# LB_BIT_i23-threshold-v03_1_1.net
KiCad netlist of a schematic drawn in EAGLE
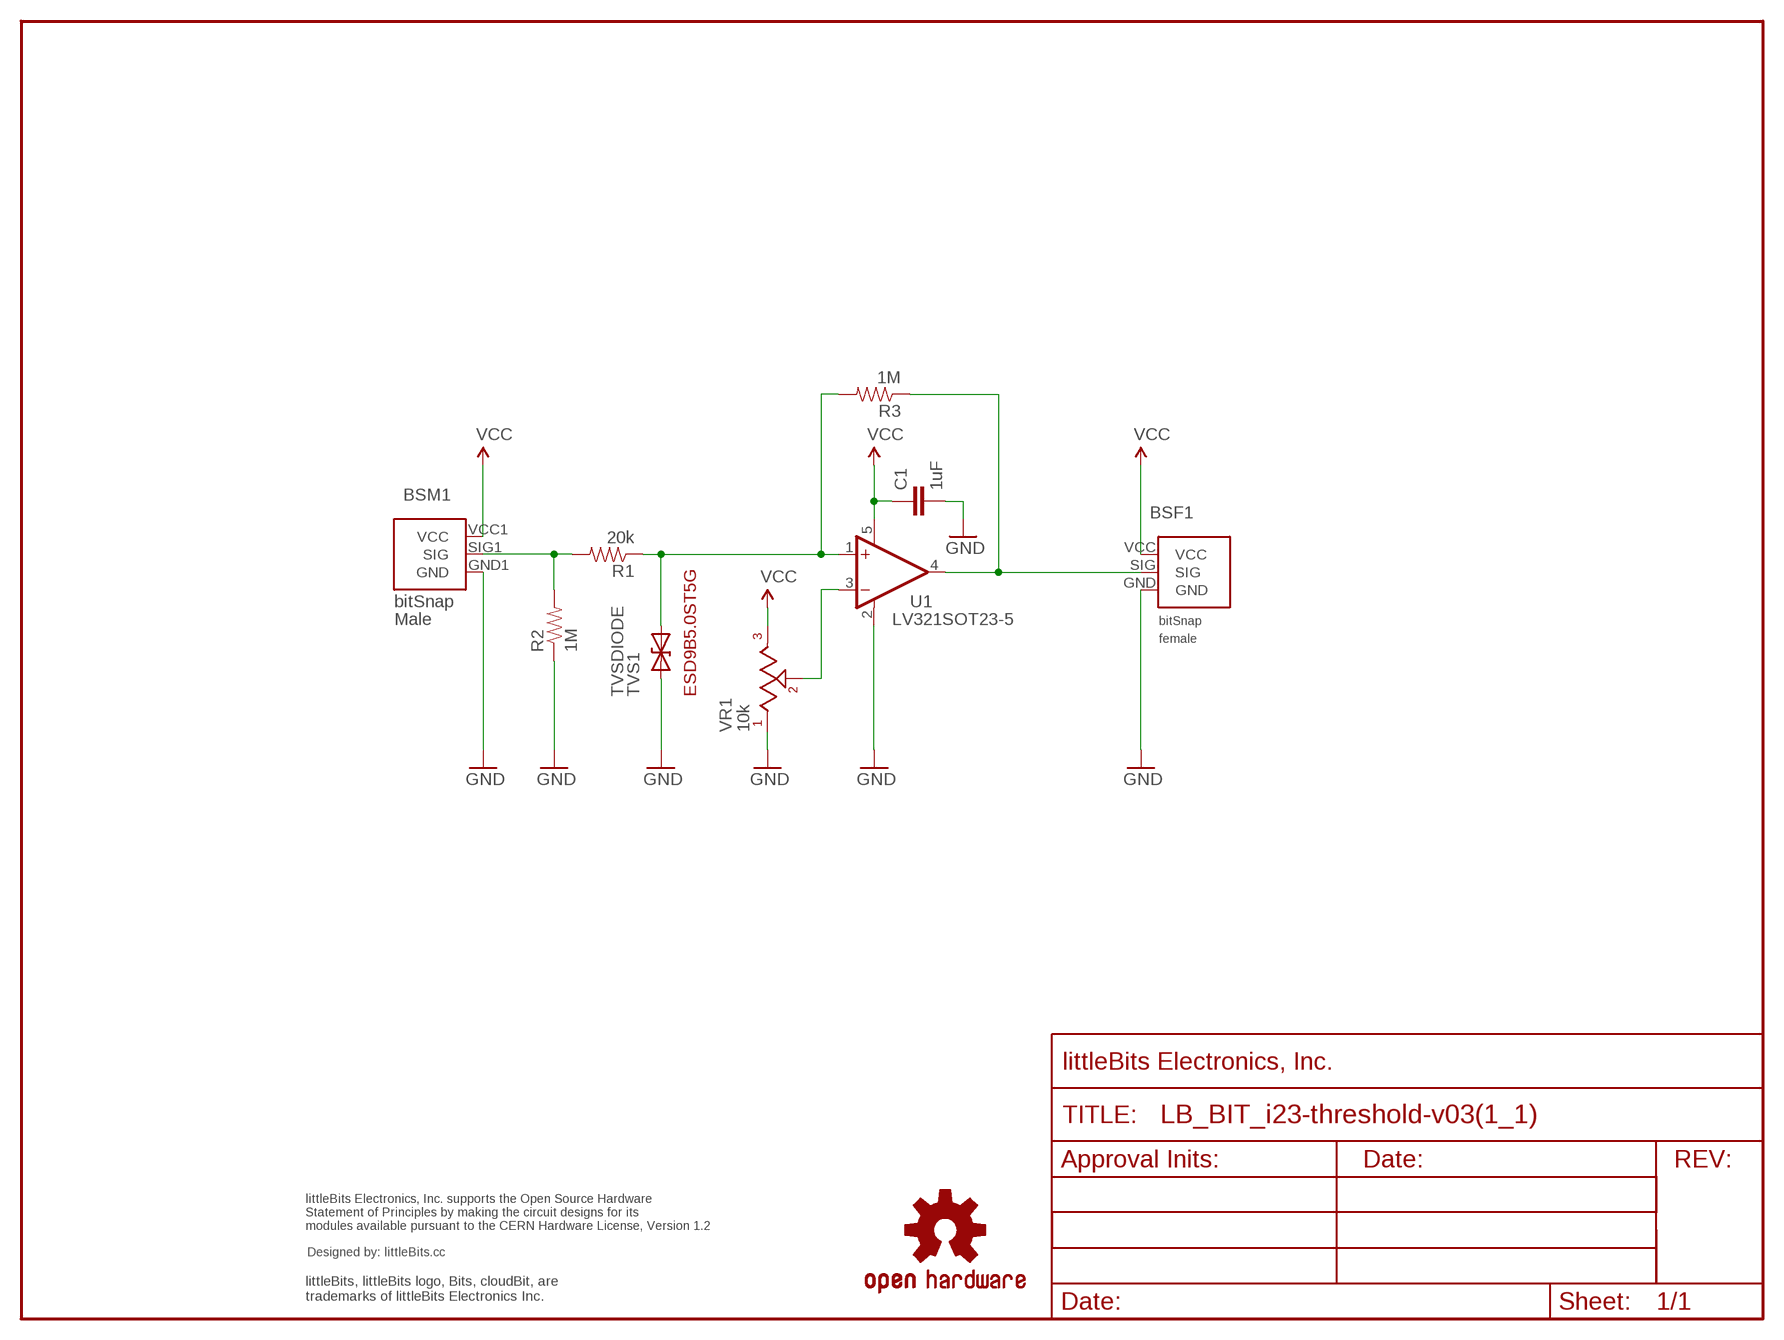
[diagram p0: schematic, sheet 1]

(export (version "E")
  (design (tool "Eeschema 10.0.6"))
  (components
    (comp (ref "BSF1")
      (value "BITSNAP_V03_FEMALE")
      (footprint "eagle-import:BITSNAP_V03_FEMALE")
      (libsource (lib "eagle-import") (part "BITSNAP_V03_FEMALE"))
    )
    (comp (ref "BSM1")
      (value "BITSNAP_V03_MALE")
      (footprint "eagle-import:BITSNAP_V03_MALE")
      (libsource (lib "eagle-import") (part "BITSNAP_V03_MALE"))
    )
    (comp (ref "C1")
      (value "1uF")
      (footprint "eagle-import:CAP-0603")
      (libsource (lib "eagle-import") (part "CAPCAP-0603"))
    )
    (comp (ref "R1")
      (value "20k")
      (footprint "eagle-import:RES-0603")
      (libsource (lib "eagle-import") (part "RESISTOR0603"))
    )
    (comp (ref "R2")
      (value "1M")
      (footprint "eagle-import:RES-0603")
      (libsource (lib "eagle-import") (part "RESISTOR0603"))
    )
    (comp (ref "R3")
      (value "1M")
      (footprint "eagle-import:RES-0603")
      (libsource (lib "eagle-import") (part "RESISTOR0603"))
    )
    (comp (ref "TVS1")
      (value "TVSDIODE")
      (footprint "eagle-import:SOD-923")
      (fields (field (name "MPN") "ESD9B5.0ST5G"))
      (libsource (lib "eagle-import") (part "DIODE-TVSSOD-923"))
    )
    (comp (ref "U$3")
      (value "OSHW-LOGOL")
      (footprint "eagle-import:OSHW-LOGO-L")
      (libsource (lib "eagle-import") (part "OSHW-LOGOL"))
    )
    (comp (ref "U$5")
      (value "FRAME-LETTER-OHWOHW")
      (footprint "eagle-import:FABDWG01-OHW")
      (libsource (lib "eagle-import") (part "FRAME-LETTER-OHWOHW"))
    )
    (comp (ref "U$31")
      (value "OSHWCREDIT")
      (footprint "eagle-import:OSHWCREDIT")
      (libsource (lib "eagle-import") (part "OSHWCREDIT"))
    )
    (comp (ref "U1")
      (value "LV321SOT23-5")
      (footprint "eagle-import:SOT23-5")
      (libsource (lib "eagle-import") (part "LV321SOT23-5"))
    )
    (comp (ref "VR1")
      (value "10k")
      (footprint "eagle-import:9MM_POT")
      (libsource (lib "eagle-import") (part "9MM_POT"))
    )
  )
  (nets
    (net (code "1") (name "GND") (class "Default")
      (node (ref "BSF1") (pin "GND") (pinfunction "GND_GND") (pintype "bidirectional"))
      (node (ref "BSM1") (pin "GND1") (pinfunction "GND_GND1") (pintype "bidirectional"))
      (node (ref "C1") (pin "2") (pinfunction "2_2") (pintype "passive"))
      (node (ref "R2") (pin "1") (pinfunction "1_1") (pintype "passive"))
      (node (ref "TVS1") (pin "1") (pinfunction "A_1") (pintype "passive"))
      (node (ref "U1") (pin "2") (pinfunction "V-_2") (pintype "power_in"))
      (node (ref "VR1") (pin "1") (pinfunction "1_1") (pintype "passive"))
    )
    (net (code "2") (name "Net-(BSM1-SIG)") (class "Default")
      (node (ref "BSM1") (pin "SIG1") (pinfunction "SIG_SIG1") (pintype "bidirectional"))
      (node (ref "R1") (pin "2") (pinfunction "2_2") (pintype "passive"))
      (node (ref "R2") (pin "2") (pinfunction "2_2") (pintype "passive"))
    )
    (net (code "3") (name "Net-(TVS1-C)") (class "Default")
      (node (ref "R1") (pin "1") (pinfunction "1_1") (pintype "passive"))
      (node (ref "R3") (pin "2") (pinfunction "2_2") (pintype "passive"))
      (node (ref "TVS1") (pin "2") (pinfunction "C_2") (pintype "passive"))
      (node (ref "U1") (pin "1") (pinfunction "+IN_1") (pintype "input"))
    )
    (net (code "4") (name "Net-(U1--IN)") (class "Default")
      (node (ref "U1") (pin "3") (pinfunction "-IN_3") (pintype "input"))
      (node (ref "VR1") (pin "2") (pinfunction "2_2") (pintype "passive"))
    )
    (net (code "5") (name "Net-(U1-OUT)") (class "Default")
      (node (ref "BSF1") (pin "SIG") (pinfunction "SIG_SIG") (pintype "bidirectional"))
      (node (ref "R3") (pin "1") (pinfunction "1_1") (pintype "passive"))
      (node (ref "U1") (pin "4") (pinfunction "OUT_4") (pintype "output"))
    )
    (net (code "6") (name "VCC") (class "Default")
      (node (ref "BSF1") (pin "VCC") (pinfunction "VCC_VCC") (pintype "bidirectional"))
      (node (ref "BSM1") (pin "VCC1") (pinfunction "VCC_VCC1") (pintype "bidirectional"))
      (node (ref "C1") (pin "1") (pinfunction "1_1") (pintype "passive"))
      (node (ref "U1") (pin "5") (pinfunction "V+_5") (pintype "power_in"))
      (node (ref "VR1") (pin "3") (pinfunction "3_3") (pintype "passive"))
    )
  )
)
